# NewPulse.net
KiCad netlist of a schematic drawn in EAGLE
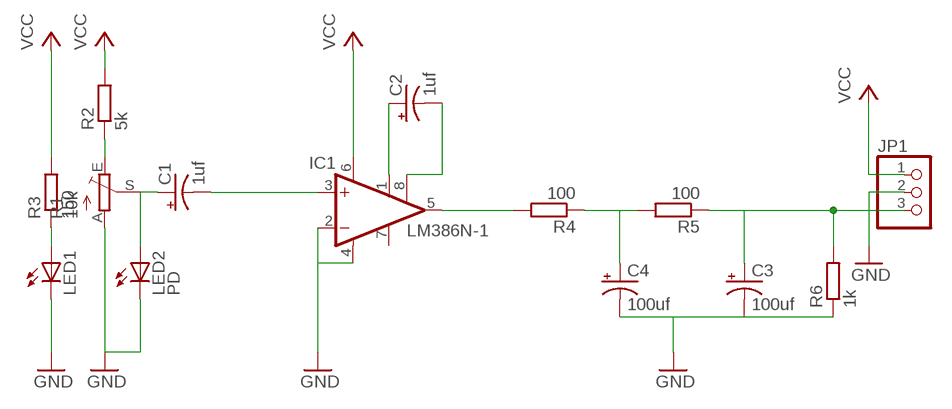
[diagram p0: schematic, sheet 1]

(export (version "E")
  (design (tool "Eeschema 10.0.6"))
  (components
    (comp (ref "C1")
      (value "1uf")
      (footprint "eagle-import:E2-5")
      (libsource (lib "eagle-import") (part "CPOL-USE2-5"))
    )
    (comp (ref "C2")
      (value "1uf")
      (footprint "eagle-import:E2-5")
      (libsource (lib "eagle-import") (part "CPOL-USE2-5"))
    )
    (comp (ref "C3")
      (value "100uf")
      (footprint "eagle-import:E2-5")
      (libsource (lib "eagle-import") (part "CPOL-USE2-5"))
    )
    (comp (ref "C4")
      (value "100uf")
      (footprint "eagle-import:E2-5")
      (libsource (lib "eagle-import") (part "CPOL-USE2-5"))
    )
    (comp (ref "IC1")
      (value "LM386N-1")
      (footprint "eagle-import:DIL08")
      (libsource (lib "eagle-import") (part "LM386?-N1"))
    )
    (comp (ref "JP1")
      (value "PINHD-1X3/90")
      (footprint "eagle-import:1X03_90")
      (libsource (lib "eagle-import") (part "PINHD-1X3/90"))
    )
    (comp (ref "LED1")
      (value "LED5MM")
      (footprint "eagle-import:LED5MM")
      (libsource (lib "eagle-import") (part "LED5MM"))
    )
    (comp (ref "LED2")
      (value "PD")
      (footprint "eagle-import:LED5MM")
      (libsource (lib "eagle-import") (part "LED5MM"))
    )
    (comp (ref "R1")
      (value "10k")
      (footprint "eagle-import:CA6V")
      (libsource (lib "eagle-import") (part "TRIM_EU-CA6V"))
    )
    (comp (ref "R2")
      (value "5k")
      (footprint "eagle-import:0207_10")
      (libsource (lib "eagle-import") (part "R-EU_0207/10"))
    )
    (comp (ref "R3")
      (value "150")
      (footprint "eagle-import:0207_10")
      (libsource (lib "eagle-import") (part "R-EU_0207/10"))
    )
    (comp (ref "R4")
      (value "100")
      (footprint "eagle-import:0207_10")
      (libsource (lib "eagle-import") (part "R-EU_0207/10"))
    )
    (comp (ref "R5")
      (value "100")
      (footprint "eagle-import:0207_10")
      (libsource (lib "eagle-import") (part "R-EU_0207/10"))
    )
    (comp (ref "R6")
      (value "1k")
      (footprint "eagle-import:0207_10")
      (libsource (lib "eagle-import") (part "R-EU_0207/10"))
    )
  )
  (nets
    (net (code "1") (name "GND") (class "Default")
      (node (ref "C3") (pin "-") (pinfunction "-_-") (pintype "passive"))
      (node (ref "C4") (pin "-") (pinfunction "-_-") (pintype "passive"))
      (node (ref "IC1") (pin "2") (pinfunction "-IN_2") (pintype "input"))
      (node (ref "IC1") (pin "4") (pinfunction "GND_4") (pintype "power_in"))
      (node (ref "JP1") (pin "2") (pinfunction "2_2") (pintype "passive"))
      (node (ref "LED1") (pin "K") (pinfunction "C_K") (pintype "passive"))
      (node (ref "LED2") (pin "K") (pinfunction "C_K") (pintype "passive"))
      (node (ref "R1") (pin "A") (pinfunction "A_A") (pintype "passive"))
      (node (ref "R6") (pin "1") (pinfunction "1_1") (pintype "passive"))
    )
    (net (code "2") (name "Net-(C1-Pad+)") (class "Default")
      (node (ref "C1") (pin "+") (pinfunction "+_+") (pintype "passive"))
      (node (ref "LED2") (pin "A") (pinfunction "A_A") (pintype "passive"))
      (node (ref "R1") (pin "S") (pinfunction "S_S") (pintype "passive"))
    )
    (net (code "3") (name "Net-(C2-Pad+)") (class "Default")
      (node (ref "C2") (pin "+") (pinfunction "+_+") (pintype "passive"))
      (node (ref "IC1") (pin "1") (pinfunction "GAIN_1") (pintype "passive"))
    )
    (net (code "4") (name "Net-(C2-Pad-)") (class "Default")
      (node (ref "C2") (pin "-") (pinfunction "-_-") (pintype "passive"))
      (node (ref "IC1") (pin "8") (pinfunction "GAIN_8") (pintype "passive"))
    )
    (net (code "5") (name "Net-(C3-Pad+)") (class "Default")
      (node (ref "C3") (pin "+") (pinfunction "+_+") (pintype "passive"))
      (node (ref "JP1") (pin "3") (pinfunction "3_3") (pintype "passive"))
      (node (ref "R5") (pin "1") (pinfunction "1_1") (pintype "passive"))
      (node (ref "R6") (pin "2") (pinfunction "2_2") (pintype "passive"))
    )
    (net (code "6") (name "Net-(C4-Pad+)") (class "Default")
      (node (ref "C4") (pin "+") (pinfunction "+_+") (pintype "passive"))
      (node (ref "R4") (pin "1") (pinfunction "1_1") (pintype "passive"))
      (node (ref "R5") (pin "2") (pinfunction "2_2") (pintype "passive"))
    )
    (net (code "7") (name "Net-(IC1-+IN)") (class "Default")
      (node (ref "C1") (pin "-") (pinfunction "-_-") (pintype "passive"))
      (node (ref "IC1") (pin "3") (pinfunction "+IN_3") (pintype "input"))
    )
    (net (code "8") (name "Net-(IC1-OUT)") (class "Default")
      (node (ref "IC1") (pin "5") (pinfunction "OUT_5") (pintype "output"))
      (node (ref "R4") (pin "2") (pinfunction "2_2") (pintype "passive"))
    )
    (net (code "9") (name "Net-(LED1-PadA)") (class "Default")
      (node (ref "LED1") (pin "A") (pinfunction "A_A") (pintype "passive"))
      (node (ref "R3") (pin "1") (pinfunction "1_1") (pintype "passive"))
    )
    (net (code "10") (name "Net-(R1-PadE)") (class "Default")
      (node (ref "R1") (pin "E") (pinfunction "E_E") (pintype "passive"))
      (node (ref "R2") (pin "1") (pinfunction "1_1") (pintype "passive"))
    )
    (net (code "11") (name "VCC") (class "Default")
      (node (ref "IC1") (pin "6") (pinfunction "VS_6") (pintype "power_in"))
      (node (ref "JP1") (pin "1") (pinfunction "1_1") (pintype "passive"))
      (node (ref "R2") (pin "2") (pinfunction "2_2") (pintype "passive"))
      (node (ref "R3") (pin "2") (pinfunction "2_2") (pintype "passive"))
    )
    (net (code "12") (name "unconnected-(IC1-BYPASS-Pad7)") (class "Default")
      (node (ref "IC1") (pin "7") (pinfunction "BYPASS_7") (pintype "passive"))
    )
  )
)
